# untitled.net
KiCad netlist of a schematic drawn in EAGLE
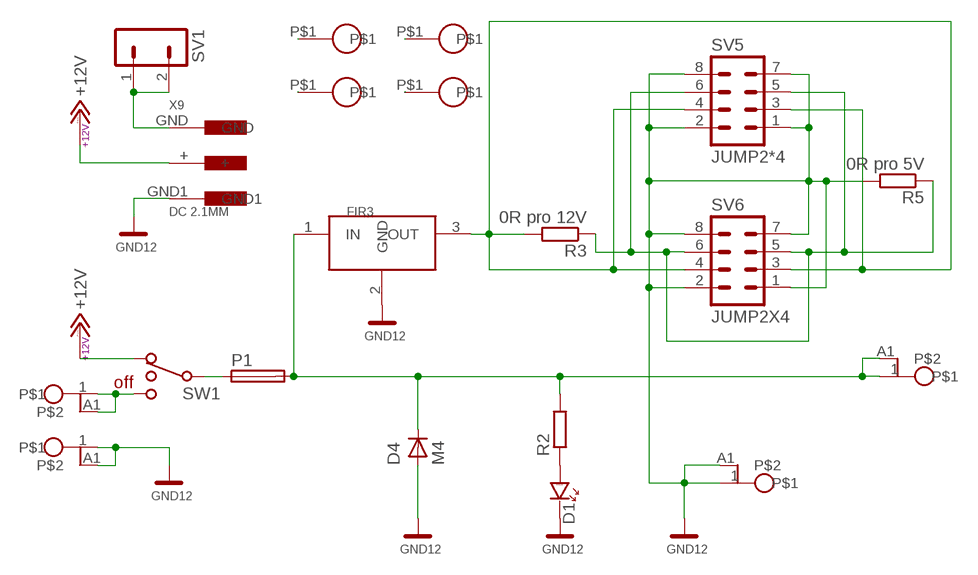
[diagram p0: schematic, sheet 1]

(export (version "E")
  (design (tool "Eeschema 10.0.6"))
  (components
    (comp (ref "D1")
      (value "D_LED_3MM")
      (footprint "eagle-import:D_LED_3")
      (libsource (lib "eagle-import") (part "D_LED_3MM"))
    )
    (comp (ref "D4")
      (value "M4")
      (footprint "eagle-import:SMA")
      (libsource (lib "eagle-import") (part "D-OB.SMA"))
    )
    (comp (ref "FIR3")
      (value "FILTR0805")
      (footprint "eagle-import:F0805")
      (libsource (lib "eagle-import") (part "FILTR0805"))
    )
    (comp (ref "P1")
      (value "POJISTKA_1812")
      (footprint "eagle-import:1812")
      (libsource (lib "eagle-import") (part "POJISTKA_1812"))
    )
    (comp (ref "R2")
      (value "R-EU_R0805")
      (footprint "eagle-import:R0805")
      (libsource (lib "eagle-import") (part "R-EU_R0805"))
    )
    (comp (ref "R3")
      (value "0R pro 12V")
      (footprint "eagle-import:R0805")
      (libsource (lib "eagle-import") (part "R-EU_R0805"))
    )
    (comp (ref "R5")
      (value "0R pro 5V")
      (footprint "eagle-import:R0805")
      (libsource (lib "eagle-import") (part "R-EU_R0805"))
    )
    (comp (ref "SV1")
      (value "MA02-1")
      (footprint "eagle-import:MA02-1")
      (libsource (lib "eagle-import") (part "MA02-1"))
    )
    (comp (ref "SV5")
      (value "JUMP2*4")
      (footprint "eagle-import:MA04-2")
      (libsource (lib "eagle-import") (part "MA04-2"))
    )
    (comp (ref "SV6")
      (value "JUMP2X4")
      (footprint "eagle-import:MA04-2")
      (libsource (lib "eagle-import") (part "MA04-2"))
    )
    (comp (ref "SW1")
      (value "PREPINAC_POSUVNY_SL19-121")
      (footprint "eagle-import:PREPINAC-POSUVNÝ")
      (libsource (lib "eagle-import") (part "PREPINAC_POSUVNY_SL19-121"))
    )
    (comp (ref "X1")
      (value "WAGO256")
      (footprint "eagle-import:WAGO256")
      (libsource (lib "eagle-import") (part "WAGO256"))
    )
    (comp (ref "X2")
      (value "WAGO256")
      (footprint "eagle-import:WAGO256")
      (libsource (lib "eagle-import") (part "WAGO256"))
    )
    (comp (ref "X3")
      (value "WAGO256")
      (footprint "eagle-import:WAGO256")
      (libsource (lib "eagle-import") (part "WAGO256"))
    )
    (comp (ref "X4")
      (value "M3")
      (footprint "eagle-import:SROUB3M")
      (libsource (lib "eagle-import") (part "SROUB3M"))
    )
    (comp (ref "X5")
      (value "M3")
      (footprint "eagle-import:SROUB3M")
      (libsource (lib "eagle-import") (part "SROUB3M"))
    )
    (comp (ref "X6")
      (value "M3")
      (footprint "eagle-import:SROUB3M")
      (libsource (lib "eagle-import") (part "SROUB3M"))
    )
    (comp (ref "X7")
      (value "M3")
      (footprint "eagle-import:SROUB3M")
      (libsource (lib "eagle-import") (part "SROUB3M"))
    )
    (comp (ref "X8")
      (value "WAGO256")
      (footprint "eagle-import:WAGO256")
      (libsource (lib "eagle-import") (part "WAGO256"))
    )
    (comp (ref "X9")
      (value "DC 2.1MM")
      (footprint "eagle-import:KONEKTOR_DC_2.1MM")
      (libsource (lib "eagle-import") (part "KONEKTOR_DC_2.1MM"))
    )
  )
  (nets
    (net (code "1") (name "+12V") (class "Default")
      (node (ref "SW1") (pin "1") (pinfunction "3_1") (pintype "passive"))
      (node (ref "X9") (pin "+") (pinfunction "+_+") (pintype "bidirectional"))
    )
    (net (code "2") (name "GND12") (class "Default")
      (node (ref "D1") (pin "K") (pinfunction "K_K") (pintype "passive"))
      (node (ref "D4") (pin "A") (pinfunction "A_A") (pintype "passive"))
      (node (ref "FIR3") (pin "2") (pinfunction "GND_2") (pintype "passive"))
      (node (ref "R5") (pin "2") (pinfunction "2_2") (pintype "passive"))
      (node (ref "SV5") (pin "1") (pinfunction "1_1") (pintype "passive"))
      (node (ref "SV5") (pin "2") (pinfunction "2_2") (pintype "passive"))
      (node (ref "SV5") (pin "7") (pinfunction "7_7") (pintype "passive"))
      (node (ref "SV5") (pin "8") (pinfunction "8_8") (pintype "passive"))
      (node (ref "SV6") (pin "1") (pinfunction "1_1") (pintype "passive"))
      (node (ref "SV6") (pin "2") (pinfunction "2_2") (pintype "passive"))
      (node (ref "SV6") (pin "7") (pinfunction "7_7") (pintype "passive"))
      (node (ref "SV6") (pin "8") (pinfunction "8_8") (pintype "passive"))
      (node (ref "X2") (pin "1") (pinfunction "P$1_1") (pintype "passive"))
      (node (ref "X2") (pin "A1") (pinfunction "P$2_A1") (pintype "passive"))
      (node (ref "X3") (pin "1") (pinfunction "P$1_1") (pintype "passive"))
      (node (ref "X3") (pin "A1") (pinfunction "P$2_A1") (pintype "passive"))
      (node (ref "X9") (pin "GND1") (pinfunction "GND1_GND1") (pintype "bidirectional"))
    )
    (net (code "3") (name "Net-(D1-PadA)") (class "Default")
      (node (ref "D1") (pin "A") (pinfunction "A_A") (pintype "passive"))
      (node (ref "R2") (pin "1") (pinfunction "1_1") (pintype "passive"))
    )
    (net (code "4") (name "Net-(D4-C)") (class "Default")
      (node (ref "D4") (pin "K") (pinfunction "C_K") (pintype "passive"))
      (node (ref "FIR3") (pin "1") (pinfunction "IN_1") (pintype "bidirectional"))
      (node (ref "P1") (pin "2") (pinfunction "2_2") (pintype "passive"))
      (node (ref "R2") (pin "2") (pinfunction "2_2") (pintype "passive"))
      (node (ref "X8") (pin "1") (pinfunction "P$1_1") (pintype "passive"))
      (node (ref "X8") (pin "A1") (pinfunction "P$2_A1") (pintype "passive"))
    )
    (net (code "5") (name "Net-(FIR3-OUT)") (class "Default")
      (node (ref "FIR3") (pin "3") (pinfunction "OUT_3") (pintype "bidirectional"))
      (node (ref "R3") (pin "2") (pinfunction "2_2") (pintype "passive"))
      (node (ref "SV5") (pin "3") (pinfunction "3_3") (pintype "passive"))
      (node (ref "SV5") (pin "4") (pinfunction "4_4") (pintype "passive"))
      (node (ref "SV6") (pin "3") (pinfunction "3_3") (pintype "passive"))
      (node (ref "SV6") (pin "4") (pinfunction "4_4") (pintype "passive"))
    )
    (net (code "6") (name "Net-(P1-Pad1)") (class "Default")
      (node (ref "P1") (pin "1") (pinfunction "1_1") (pintype "passive"))
      (node (ref "SW1") (pin "2") (pinfunction "2_2") (pintype "passive"))
    )
    (net (code "7") (name "Net-(R3-Pad1)") (class "Default")
      (node (ref "R3") (pin "1") (pinfunction "1_1") (pintype "passive"))
      (node (ref "R5") (pin "1") (pinfunction "1_1") (pintype "passive"))
      (node (ref "SV5") (pin "5") (pinfunction "5_5") (pintype "passive"))
      (node (ref "SV5") (pin "6") (pinfunction "6_6") (pintype "passive"))
      (node (ref "SV6") (pin "5") (pinfunction "5_5") (pintype "passive"))
      (node (ref "SV6") (pin "6") (pinfunction "6_6") (pintype "passive"))
    )
    (net (code "8") (name "Net-(SV1-3)") (class "Default")
      (node (ref "SV1") (pin "1") (pinfunction "1_1") (pintype "passive"))
      (node (ref "SV1") (pin "2") (pinfunction "3_2") (pintype "passive"))
      (node (ref "X9") (pin "GND") (pinfunction "GND_GND") (pintype "bidirectional"))
    )
    (net (code "9") (name "Net-(SW1-1)") (class "Default")
      (node (ref "SW1") (pin "3") (pinfunction "1_3") (pintype "passive"))
      (node (ref "X1") (pin "1") (pinfunction "P$1_1") (pintype "passive"))
      (node (ref "X1") (pin "A1") (pinfunction "P$2_A1") (pintype "passive"))
    )
    (net (code "10") (name "unconnected-(X4-PadP$1)") (class "Default")
      (node (ref "X4") (pin "P$1") (pinfunction "P$1_P$1") (pintype "passive"))
    )
    (net (code "11") (name "unconnected-(X5-PadP$1)") (class "Default")
      (node (ref "X5") (pin "P$1") (pinfunction "P$1_P$1") (pintype "passive"))
    )
    (net (code "12") (name "unconnected-(X6-PadP$1)") (class "Default")
      (node (ref "X6") (pin "P$1") (pinfunction "P$1_P$1") (pintype "passive"))
    )
    (net (code "13") (name "unconnected-(X7-PadP$1)") (class "Default")
      (node (ref "X7") (pin "P$1") (pinfunction "P$1_P$1") (pintype "passive"))
    )
  )
)
